# LTEW_User_Interface.net
KiCad netlist of a schematic drawn in Altium Designer
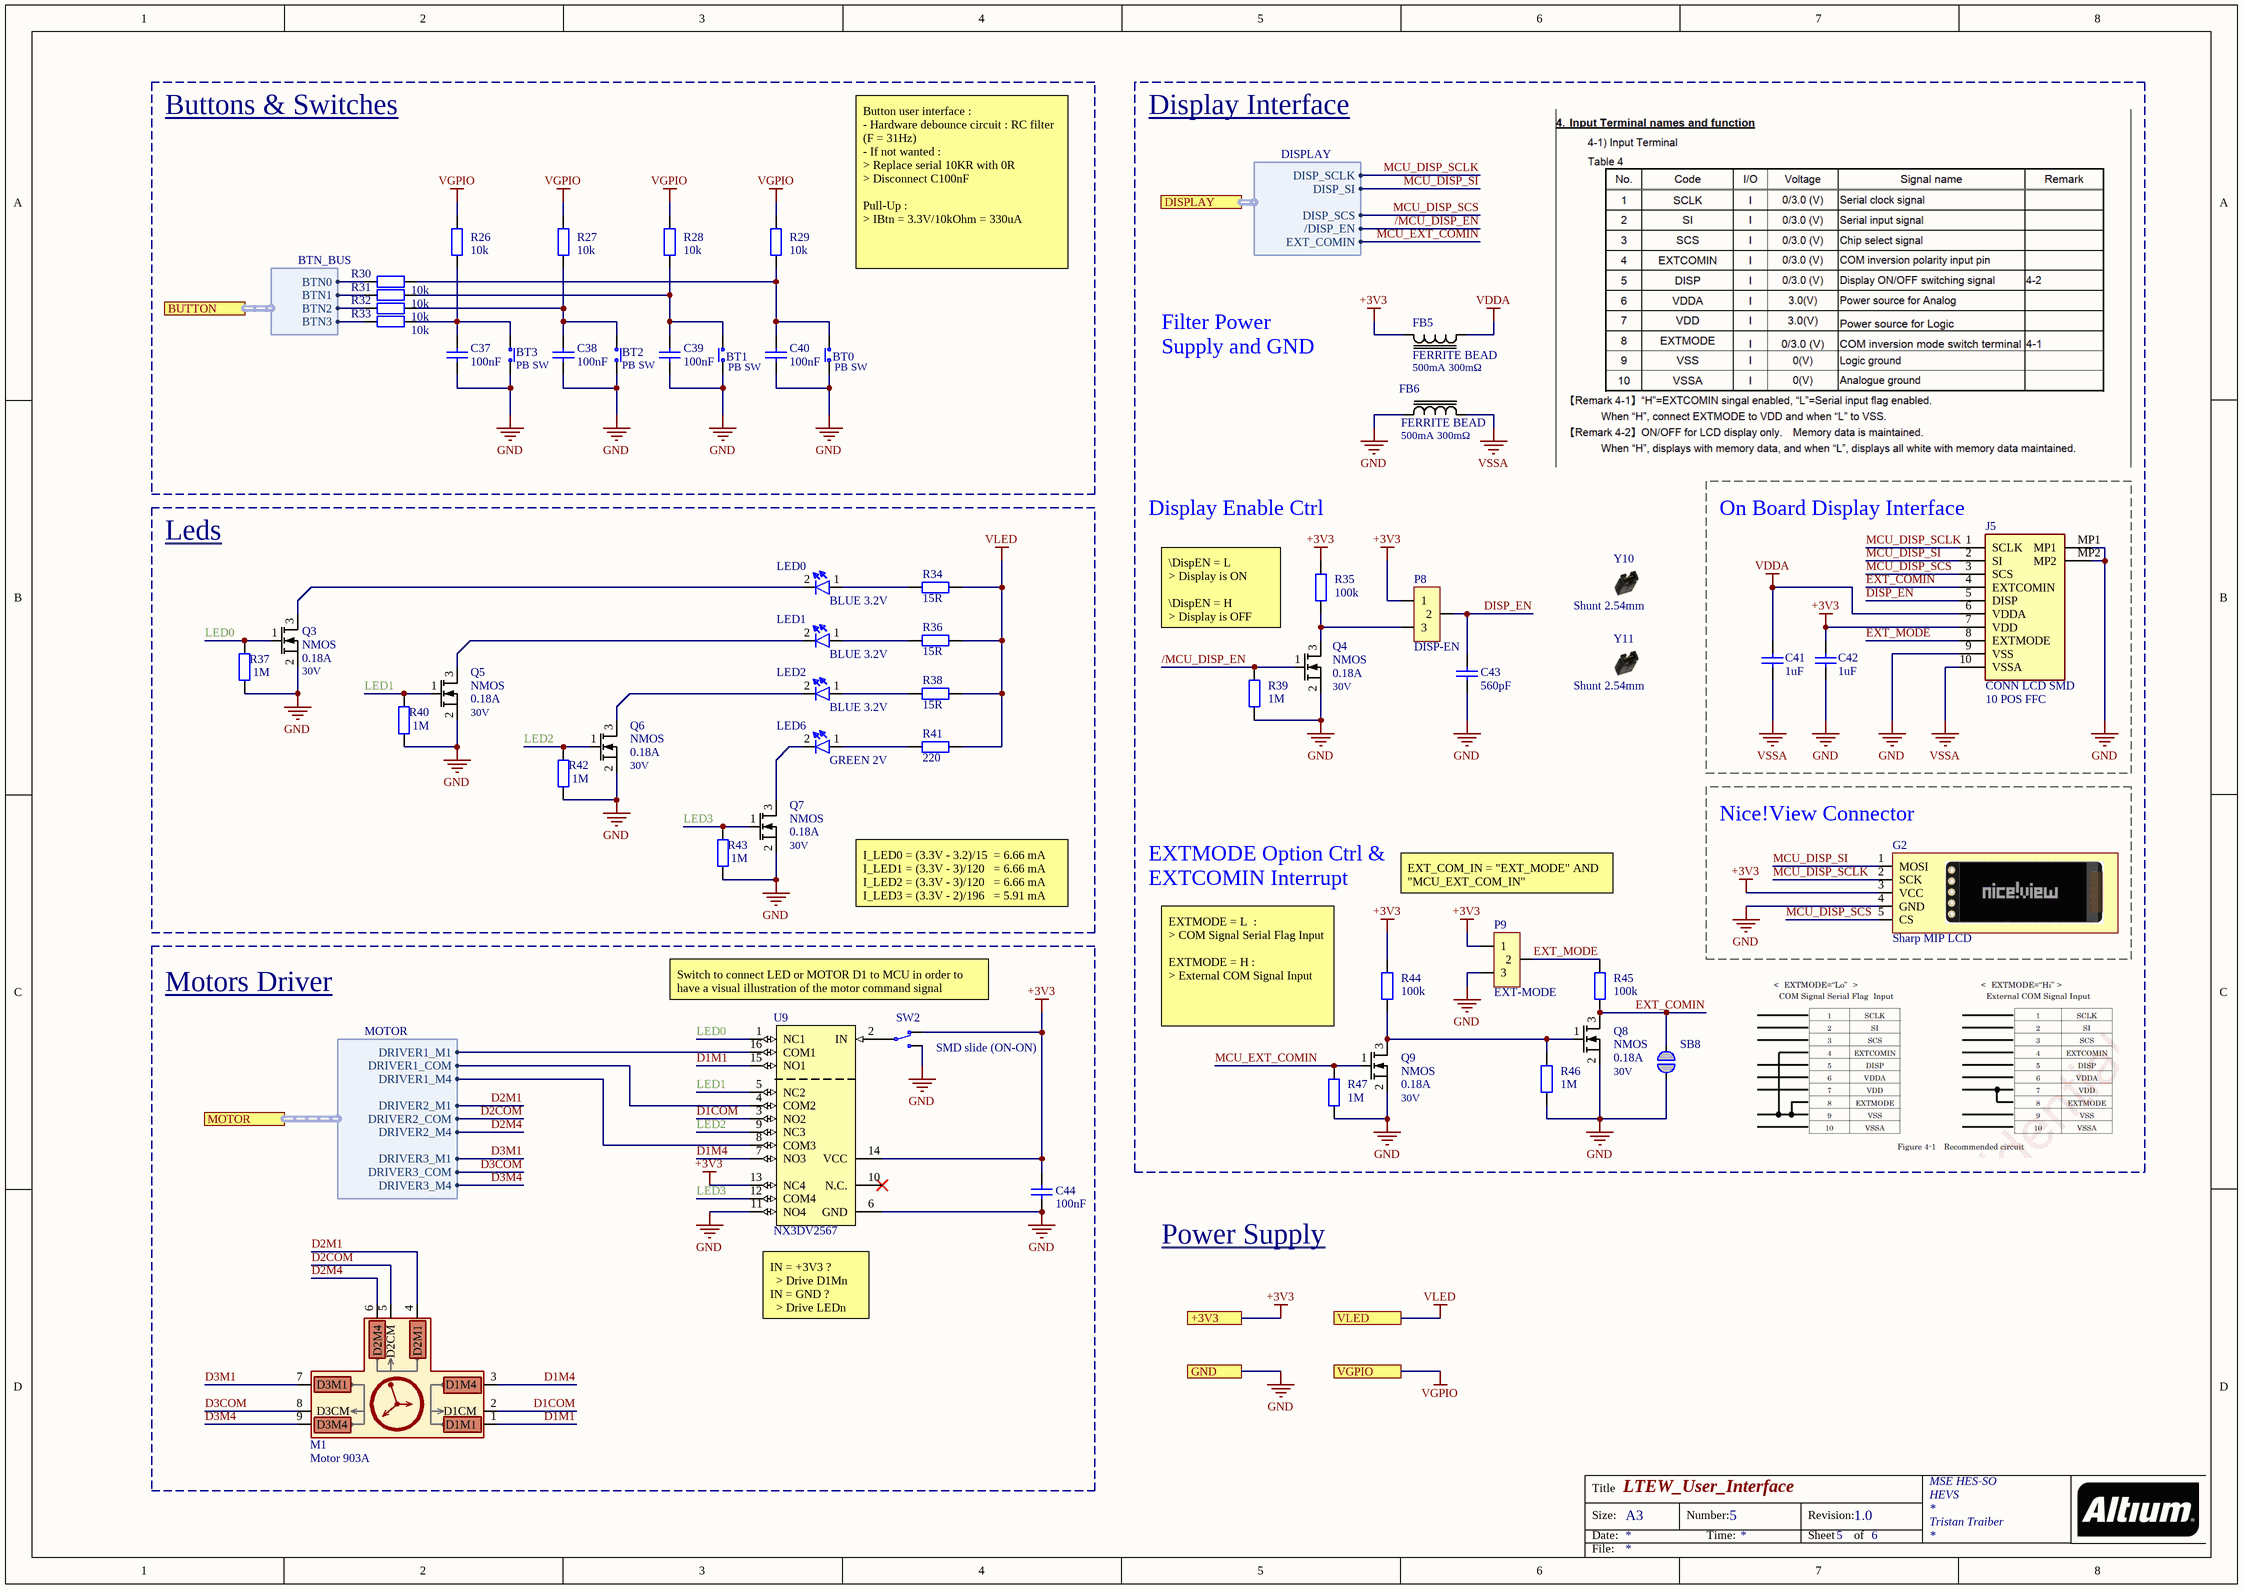
[diagram p0: LTEW_User_Interface.SchDoc]

(export (version "E")
  (design (tool "Eeschema 10.0.6"))
  (components
    (comp (ref "BT0")
      (value "PB SW")
      (footprint "Switch-PB-SMD-BT0")
      (description "Tactile Switch, SPNO, SMD, 160gf, 6.2x6.3x2.5mm")
      (fields (field (name "MANUFACTURER_PART_NUMBER") "SKHUALE010"))
      (libsource (lib "LTEWlib") (part "SW_SMD_PB"))
    )
    (comp (ref "BT1")
      (value "PB SW")
      (footprint "Switch-PB-SMD-BT1")
      (description "Tactile Switch, SPNO, SMD, 160gf, 6.2x6.3x2.5mm")
      (fields (field (name "MANUFACTURER_PART_NUMBER") "SKHUALE010"))
      (libsource (lib "LTEWlib") (part "SW_SMD_PB"))
    )
    (comp (ref "BT2")
      (value "PB SW")
      (footprint "Switch-PB-SMD-BT2")
      (description "Tactile Switch, SPNO, SMD, 160gf, 6.2x6.3x2.5mm")
      (fields (field (name "MANUFACTURER_PART_NUMBER") "SKHUALE010"))
      (libsource (lib "LTEWlib") (part "SW_SMD_PB"))
    )
    (comp (ref "BT3")
      (value "PB SW")
      (footprint "Switch-PB-SMD-BT3")
      (description "Tactile Switch, SPNO, SMD, 160gf, 6.2x6.3x2.5mm")
      (fields (field (name "MANUFACTURER_PART_NUMBER") "SKHUALE010"))
      (libsource (lib "LTEWlib") (part "SW_SMD_PB"))
    )
    (comp (ref "C37")
      (value "100nF")
      (footprint "C0603")
      (description "0.1 µF ±10% 25V Condensateurs céramique X7R 0603 (1608 métrique)")
      (fields (field (name "MANUFACTURER_PART_NUMBER") "CL10B104KA8NNNC"))
      (libsource (lib "LTEWlib") (part "C_100n"))
    )
    (comp (ref "C38")
      (value "100nF")
      (footprint "C0603")
      (description "0.1 µF ±10% 25V Condensateurs céramique X7R 0603 (1608 métrique)")
      (fields (field (name "MANUFACTURER_PART_NUMBER") "CL10B104KA8NNNC"))
      (libsource (lib "LTEWlib") (part "C_100n"))
    )
    (comp (ref "C39")
      (value "100nF")
      (footprint "C0603")
      (description "0.1 µF ±10% 25V Condensateurs céramique X7R 0603 (1608 métrique)")
      (fields (field (name "MANUFACTURER_PART_NUMBER") "CL10B104KA8NNNC"))
      (libsource (lib "LTEWlib") (part "C_100n"))
    )
    (comp (ref "C40")
      (value "100nF")
      (footprint "C0603")
      (description "0.1 µF ±10% 25V Condensateurs céramique X7R 0603 (1608 métrique)")
      (fields (field (name "MANUFACTURER_PART_NUMBER") "CL10B104KA8NNNC"))
      (libsource (lib "LTEWlib") (part "C_100n"))
    )
    (comp (ref "C41")
      (value "1uF")
      (footprint "C0603")
      (description "1 µF ±10% 25V Ceramic Capacitor X7R 0603 (1608 Metric)")
      (fields (field (name "MANUFACTURER_PART_NUMBER") "CL10B105KA8NNNC"))
      (libsource (lib "LTEWlib") (part "C_1u"))
    )
    (comp (ref "C42")
      (value "1uF")
      (footprint "C0603")
      (description "1 µF ±10% 25V Ceramic Capacitor X7R 0603 (1608 Metric)")
      (fields (field (name "MANUFACTURER_PART_NUMBER") "CL10B105KA8NNNC"))
      (libsource (lib "LTEWlib") (part "C_1u"))
    )
    (comp (ref "C43")
      (value "560pF")
      (footprint "C0603")
      (description "560 pF ±5% 25V Ceramic Capacitor C0G, NP0 0603 (1608 Metric)")
      (fields (field (name "MANUFACTURER_PART_NUMBER") "CC0603JRNPO8BN561"))
      (libsource (lib "LTEWlib") (part "C_560p"))
    )
    (comp (ref "C44")
      (value "100nF")
      (footprint "C0603")
      (description "0.1 µF ±10% 25V Condensateurs céramique X7R 0603 (1608 métrique)")
      (fields (field (name "MANUFACTURER_PART_NUMBER") "CL10B104KA8NNNC"))
      (libsource (lib "LTEWlib") (part "C_100n"))
    )
    (comp (ref "FB5")
      (value "FERRITE BEAD")
      (footprint "LTEWlib:BEADC2012X110N")
      (description "600 Ohms @ 100 MHz 1 Power, Signal Line Ferrite Bead 0805 (2012 Metric) 500mA 300mOhm")
      (fields
        (field (name "MANUFACTURER_PART_NUMBER") "HZ0805E601R-10")
        (field (name "ALTIUM_VALUE") "500mA 300mΩ")
      )
      (libsource (lib "LTEWlib") (part "L_FerritBead"))
    )
    (comp (ref "FB6")
      (value "FERRITE BEAD")
      (footprint "LTEWlib:BEADC2012X110N")
      (description "600 Ohms @ 100 MHz 1 Power, Signal Line Ferrite Bead 0805 (2012 Metric) 500mA 300mOhm")
      (fields
        (field (name "MANUFACTURER_PART_NUMBER") "HZ0805E601R-10")
        (field (name "ALTIUM_VALUE") "500mA 300mΩ")
      )
      (libsource (lib "LTEWlib") (part "L_FerritBead"))
    )
    (comp (ref "G2")
      (value "Sharp MIP LCD")
      (footprint "SHARP_MIP_LCD")
      (description "503535 3.8v 580mAh round lipo battery cells\r\n(Order : shorturl.at/tEFMZ)")
      (fields (field (name "MANUFACTURER_PART_NUMBER") "LS011B7DH03"))
      (libsource (lib "LTEWlib") (part "Display"))
    )
    (comp (ref "J5")
      (value "CONN LCD SMD")
      (footprint "LTEWlib:FH12A10S05SH55")
      (description "10 Position FFC, FPC Connector Contacts, Top 0.020\" (0.50mm) Surface Mount, Right Angle")
      (fields
        (field (name "MANUFACTURER_PART_NUMBER") "FH12A-10S-0.5SH(55)")
        (field (name "ALTIUM_VALUE") "10 POS FFC")
      )
      (libsource (lib "LTEWlib") (part "CONN_LCD_FFC12"))
    )
    (comp (ref "LED0")
      (value "BLUE 3.2V")
      (footprint "LTEWlib:LEDC1608X80N")
      (description "Blue 470nm LED Indication - Discrete 3.2V 0603 (1608 Metric)")
      (fields (field (name "MANUFACTURER_PART_NUMBER") "150060BS75000"))
      (libsource (lib "LTEWlib") (part "LED_B"))
    )
    (comp (ref "LED1")
      (value "BLUE 3.2V")
      (footprint "LTEWlib:LEDC1608X80N")
      (description "Blue 470nm LED Indication - Discrete 3.2V 0603 (1608 Metric)")
      (fields (field (name "MANUFACTURER_PART_NUMBER") "150060BS75000"))
      (libsource (lib "LTEWlib") (part "LED_B"))
    )
    (comp (ref "LED2")
      (value "BLUE 3.2V")
      (footprint "LTEWlib:LEDC1608X80N")
      (description "Blue 470nm LED Indication - Discrete 3.2V 0603 (1608 Metric)")
      (fields (field (name "MANUFACTURER_PART_NUMBER") "150060BS75000"))
      (libsource (lib "LTEWlib") (part "LED_B"))
    )
    (comp (ref "LED6")
      (value "GREEN 2V")
      (footprint "LTEWlib:LEDC1608X80N")
      (description "Green 570nm LED Indication - Discrete 2V 0603 (1608 Metric)")
      (fields (field (name "MANUFACTURER_PART_NUMBER") "150060VS75000"))
      (libsource (lib "LTEWlib") (part "LED_G"))
    )
    (comp (ref "M1")
      (value "Motor 903A")
      (footprint "MOTOR")
      (description "Titan 903A : 3 Hands Bidirectional, independent motor")
      (fields (field (name "PUBLISHER") "Altium Limited"))
      (libsource (lib "LTEWlib") (part "MOTOR_903A"))
    )
    (comp (ref "P8")
      (value "DISP-EN")
      (footprint "HDR1X3 - DISP_EN")
      (description "Header, 3-Pin")
      (fields (field (name "MANUFACTURER_PART_NUMBER") "M20-9990345"))
      (libsource (lib "LTEWlib") (part "H_3POS"))
    )
    (comp (ref "P9")
      (value "EXT-MODE")
      (footprint "HDR1X3 - EXT_MODE")
      (description "Header, 3-Pin")
      (fields (field (name "MANUFACTURER_PART_NUMBER") "M20-9990345"))
      (libsource (lib "LTEWlib") (part "H_3POS"))
    )
    (comp (ref "Q3")
      (value "NMOS")
      (footprint "LTEWlib:SOT65P210X110-3N")
      (description "N-Channel 30 V 180mA (Ta) 260mW (Ta), 1.1W (Tc) Surface Mount SOT-323")
      (fields
        (field (name "MANUFACTURER_PART_NUMBER") "NX3020NAKW")
        (field (name "VALUE2") "0.18A")
        (field (name "ALTIUM_VALUE") "30V")
      )
      (libsource (lib "LTEWlib") (part "MOS-N"))
    )
    (comp (ref "Q4")
      (value "NMOS")
      (footprint "LTEWlib:SOT65P210X110-3N")
      (description "N-Channel 30 V 180mA (Ta) 260mW (Ta), 1.1W (Tc) Surface Mount SOT-323")
      (fields
        (field (name "MANUFACTURER_PART_NUMBER") "NX3020NAKW")
        (field (name "VALUE2") "0.18A")
        (field (name "ALTIUM_VALUE") "30V")
      )
      (libsource (lib "LTEWlib") (part "MOS-N"))
    )
    (comp (ref "Q5")
      (value "NMOS")
      (footprint "LTEWlib:SOT65P210X110-3N")
      (description "N-Channel 30 V 180mA (Ta) 260mW (Ta), 1.1W (Tc) Surface Mount SOT-323")
      (fields
        (field (name "MANUFACTURER_PART_NUMBER") "NX3020NAKW")
        (field (name "VALUE2") "0.18A")
        (field (name "ALTIUM_VALUE") "30V")
      )
      (libsource (lib "LTEWlib") (part "MOS-N"))
    )
    (comp (ref "Q6")
      (value "NMOS")
      (footprint "LTEWlib:SOT65P210X110-3N")
      (description "N-Channel 30 V 180mA (Ta) 260mW (Ta), 1.1W (Tc) Surface Mount SOT-323")
      (fields
        (field (name "MANUFACTURER_PART_NUMBER") "NX3020NAKW")
        (field (name "VALUE2") "0.18A")
        (field (name "ALTIUM_VALUE") "30V")
      )
      (libsource (lib "LTEWlib") (part "MOS-N"))
    )
    (comp (ref "Q7")
      (value "NMOS")
      (footprint "LTEWlib:SOT65P210X110-3N")
      (description "N-Channel 30 V 180mA (Ta) 260mW (Ta), 1.1W (Tc) Surface Mount SOT-323")
      (fields
        (field (name "MANUFACTURER_PART_NUMBER") "NX3020NAKW")
        (field (name "VALUE2") "0.18A")
        (field (name "ALTIUM_VALUE") "30V")
      )
      (libsource (lib "LTEWlib") (part "MOS-N"))
    )
    (comp (ref "Q8")
      (value "NMOS")
      (footprint "LTEWlib:SOT65P210X110-3N")
      (description "N-Channel 30 V 180mA (Ta) 260mW (Ta), 1.1W (Tc) Surface Mount SOT-323")
      (fields
        (field (name "MANUFACTURER_PART_NUMBER") "NX3020NAKW")
        (field (name "VALUE2") "0.18A")
        (field (name "ALTIUM_VALUE") "30V")
      )
      (libsource (lib "LTEWlib") (part "MOS-N"))
    )
    (comp (ref "Q9")
      (value "NMOS")
      (footprint "LTEWlib:SOT65P210X110-3N")
      (description "N-Channel 30 V 180mA (Ta) 260mW (Ta), 1.1W (Tc) Surface Mount SOT-323")
      (fields
        (field (name "MANUFACTURER_PART_NUMBER") "NX3020NAKW")
        (field (name "VALUE2") "0.18A")
        (field (name "ALTIUM_VALUE") "30V")
      )
      (libsource (lib "LTEWlib") (part "MOS-N"))
    )
    (comp (ref "R26")
      (value "10k")
      (footprint "RES0603")
      (description "10 kOhms ±1% 0.1W, 1/10W Chip Resistor 0603 (1608 Metric) Moisture Resistant Thick Film")
      (fields (field (name "MANUFACTURER_PART_NUMBER") "RC0805FR-0710KL"))
      (libsource (lib "LTEWlib") (part "R_10k"))
    )
    (comp (ref "R27")
      (value "10k")
      (footprint "RES0603")
      (description "10 kOhms ±1% 0.1W, 1/10W Chip Resistor 0603 (1608 Metric) Moisture Resistant Thick Film")
      (fields (field (name "MANUFACTURER_PART_NUMBER") "RC0805FR-0710KL"))
      (libsource (lib "LTEWlib") (part "R_10k"))
    )
    (comp (ref "R28")
      (value "10k")
      (footprint "RES0603")
      (description "10 kOhms ±1% 0.1W, 1/10W Chip Resistor 0603 (1608 Metric) Moisture Resistant Thick Film")
      (fields (field (name "MANUFACTURER_PART_NUMBER") "RC0805FR-0710KL"))
      (libsource (lib "LTEWlib") (part "R_10k"))
    )
    (comp (ref "R29")
      (value "10k")
      (footprint "RES0603")
      (description "10 kOhms ±1% 0.1W, 1/10W Chip Resistor 0603 (1608 Metric) Moisture Resistant Thick Film")
      (fields (field (name "MANUFACTURER_PART_NUMBER") "RC0805FR-0710KL"))
      (libsource (lib "LTEWlib") (part "R_10k"))
    )
    (comp (ref "R30")
      (value "10k")
      (footprint "RES0603")
      (description "10 kOhms ±1% 0.1W, 1/10W Chip Resistor 0603 (1608 Metric) Moisture Resistant Thick Film")
      (fields (field (name "MANUFACTURER_PART_NUMBER") "RC0805FR-0710KL"))
      (libsource (lib "") (part "R_10k_1"))
    )
    (comp (ref "R31")
      (value "10k")
      (footprint "RES0603")
      (description "10 kOhms ±1% 0.1W, 1/10W Chip Resistor 0603 (1608 Metric) Moisture Resistant Thick Film")
      (fields (field (name "MANUFACTURER_PART_NUMBER") "RC0805FR-0710KL"))
      (libsource (lib "") (part "R_10k_1"))
    )
    (comp (ref "R32")
      (value "10k")
      (footprint "RES0603")
      (description "10 kOhms ±1% 0.1W, 1/10W Chip Resistor 0603 (1608 Metric) Moisture Resistant Thick Film")
      (fields (field (name "MANUFACTURER_PART_NUMBER") "RC0805FR-0710KL"))
      (libsource (lib "") (part "R_10k_1"))
    )
    (comp (ref "R33")
      (value "10k")
      (footprint "RES0603")
      (description "10 kOhms ±1% 0.1W, 1/10W Chip Resistor 0603 (1608 Metric) Moisture Resistant Thick Film")
      (fields (field (name "MANUFACTURER_PART_NUMBER") "RC0805FR-0710KL"))
      (libsource (lib "") (part "R_10k_1"))
    )
    (comp (ref "R34")
      (value "15R")
      (footprint "RES0603")
      (description "15 Ohms ±1% 0.1W, 1/10W Chip Resistor 0603 (1608 Metric) Moisture Resistant Thick Film")
      (fields (field (name "MANUFACTURER_PART_NUMBER") "RC0603FR-0715RL"))
      (libsource (lib "LTEWlib") (part "R_15"))
    )
    (comp (ref "R35")
      (value "100k")
      (footprint "RES0603")
      (description "RES SMD 100K OHM 1% 1/8W 0603")
      (fields (field (name "MANUFACTURER_PART_NUMBER") "RC0805FR-07100KL"))
      (libsource (lib "LTEWlib") (part "R_100k"))
    )
    (comp (ref "R36")
      (value "15R")
      (footprint "RES0603")
      (description "15 Ohms ±1% 0.1W, 1/10W Chip Resistor 0603 (1608 Metric) Moisture Resistant Thick Film")
      (fields (field (name "MANUFACTURER_PART_NUMBER") "RC0603FR-0715RL"))
      (libsource (lib "LTEWlib") (part "R_15"))
    )
    (comp (ref "R37")
      (value "1M")
      (footprint "RES0603")
      (description "1 MOhms ±1% 0.1W, 1/10W Chip Resistor 0603 (1608 Metric) Automotive AEC-Q200 Thick Film")
      (fields (field (name "MANUFACTURER_PART_NUMBER") "ERJ-3EKF1004V"))
      (libsource (lib "LTEWlib") (part "R_1M"))
    )
    (comp (ref "R38")
      (value "15R")
      (footprint "RES0603")
      (description "15 Ohms ±1% 0.1W, 1/10W Chip Resistor 0603 (1608 Metric) Moisture Resistant Thick Film")
      (fields (field (name "MANUFACTURER_PART_NUMBER") "RC0603FR-0715RL"))
      (libsource (lib "LTEWlib") (part "R_15"))
    )
    (comp (ref "R39")
      (value "1M")
      (footprint "RES0603")
      (description "1 MOhms ±1% 0.1W, 1/10W Chip Resistor 0603 (1608 Metric) Automotive AEC-Q200 Thick Film")
      (fields (field (name "MANUFACTURER_PART_NUMBER") "ERJ-3EKF1004V"))
      (libsource (lib "LTEWlib") (part "R_1M"))
    )
    (comp (ref "R40")
      (value "1M")
      (footprint "RES0603")
      (description "1 MOhms ±1% 0.1W, 1/10W Chip Resistor 0603 (1608 Metric) Automotive AEC-Q200 Thick Film")
      (fields (field (name "MANUFACTURER_PART_NUMBER") "ERJ-3EKF1004V"))
      (libsource (lib "LTEWlib") (part "R_1M"))
    )
    (comp (ref "R41")
      (value "220")
      (footprint "RES0603")
      (description "220 Ohms ±1% 0.1W, 1/10W Chip Resistor 0603 (1608 Metric) Moisture Resistant Thick Film")
      (fields (field (name "MANUFACTURER_PART_NUMBER") "CR0603-FX-3300ELF"))
      (libsource (lib "LTEWlib") (part "R_220"))
    )
    (comp (ref "R42")
      (value "1M")
      (footprint "RES0603")
      (description "1 MOhms ±1% 0.1W, 1/10W Chip Resistor 0603 (1608 Metric) Automotive AEC-Q200 Thick Film")
      (fields (field (name "MANUFACTURER_PART_NUMBER") "ERJ-3EKF1004V"))
      (libsource (lib "LTEWlib") (part "R_1M"))
    )
    (comp (ref "R43")
      (value "1M")
      (footprint "RES0603")
      (description "1 MOhms ±1% 0.1W, 1/10W Chip Resistor 0603 (1608 Metric) Automotive AEC-Q200 Thick Film")
      (fields (field (name "MANUFACTURER_PART_NUMBER") "ERJ-3EKF1004V"))
      (libsource (lib "LTEWlib") (part "R_1M"))
    )
    (comp (ref "R44")
      (value "100k")
      (footprint "RES0603")
      (description "RES SMD 100K OHM 1% 1/8W 0603")
      (fields (field (name "MANUFACTURER_PART_NUMBER") "RC0805FR-07100KL"))
      (libsource (lib "LTEWlib") (part "R_100k"))
    )
    (comp (ref "R45")
      (value "100k")
      (footprint "RES0603")
      (description "RES SMD 100K OHM 1% 1/8W 0603")
      (fields (field (name "MANUFACTURER_PART_NUMBER") "RC0805FR-07100KL"))
      (libsource (lib "LTEWlib") (part "R_100k"))
    )
    (comp (ref "R46")
      (value "1M")
      (footprint "RES0603")
      (description "1 MOhms ±1% 0.1W, 1/10W Chip Resistor 0603 (1608 Metric) Automotive AEC-Q200 Thick Film")
      (fields (field (name "MANUFACTURER_PART_NUMBER") "ERJ-3EKF1004V"))
      (libsource (lib "LTEWlib") (part "R_1M"))
    )
    (comp (ref "R47")
      (value "1M")
      (footprint "RES0603")
      (description "1 MOhms ±1% 0.1W, 1/10W Chip Resistor 0603 (1608 Metric) Automotive AEC-Q200 Thick Film")
      (fields (field (name "MANUFACTURER_PART_NUMBER") "ERJ-3EKF1004V"))
      (libsource (lib "LTEWlib") (part "R_1M"))
    )
    (comp (ref "SB8")
      (value "Solderbridge")
      (footprint "Solderbridge")
      (fields (field (name "MANUFACTURER") "N.A."))
      (libsource (lib "pca10090") (part "Solderbridge"))
    )
    (comp (ref "SW2")
      (value "SMD slide (ON-ON)")
      (footprint "CJS-120xA - M/L")
      (description "SMD slide Switch (ON-ON)")
      (fields (field (name "MANUFACTURER_PART_NUMBER") "CJS-1200TA"))
      (libsource (lib "LTEWlib") (part "SW_2POS"))
    )
    (comp (ref "U9")
      (value "NX3DV2567")
      (footprint "XQFN40P180X260X50-16N")
      (description "Low-ohmic four-pole double-throw analog switch")
      (fields (field (name "MANUFACTURER PART NUMBER") "NX3DV2567GU"))
      (libsource (lib "LTEWlib") (part "NX3DV2567GU"))
    )
    (comp (ref "Y10")
      (value "Shunt 2.54mm")
      (footprint "Shunt_2.54mm_Horizontal")
      (description "Shunt Jumper 2.54mm Black")
      (fields (field (name "MANUFACTURER PART NUMBER") "SPC02SYAN"))
      (libsource (lib "LTEWlib") (part "SHUNT JUMPER 2.54mm BLACK GOLD Horizontal"))
    )
    (comp (ref "Y11")
      (value "Shunt 2.54mm")
      (footprint "Shunt_2.54mm_Horizontal")
      (description "Shunt Jumper 2.54mm Black")
      (fields (field (name "MANUFACTURER PART NUMBER") "SPC02SYAN"))
      (libsource (lib "LTEWlib") (part "SHUNT JUMPER 2.54mm BLACK GOLD Horizontal"))
    )
  )
  (nets
    (net (code "4") (name "+3V3") (class "Default")
      (node (ref "C42") (pin "2") (pinfunction "2_2") (pintype "passive"))
      (node (ref "C44") (pin "2") (pinfunction "2_2") (pintype "passive"))
      (node (ref "FB5") (pin "2") (pinfunction "2_2") (pintype "passive"))
      (node (ref "G2") (pin "3") (pinfunction "VCC_3") (pintype "passive"))
      (node (ref "J5") (pin "7") (pinfunction "VDD_7") (pintype "passive"))
      (node (ref "P8") (pin "1") (pinfunction "1_1") (pintype "passive"))
      (node (ref "P9") (pin "1") (pinfunction "1_1") (pintype "passive"))
      (node (ref "R35") (pin "2") (pinfunction "2_2") (pintype "passive"))
      (node (ref "R44") (pin "2") (pinfunction "2_2") (pintype "passive"))
      (node (ref "SW2") (pin "1") (pinfunction "N.C_1") (pintype "passive"))
      (node (ref "U9") (pin "13") (pinfunction "NC4_13") (pintype "bidirectional"))
      (node (ref "U9") (pin "14") (pinfunction "VCC_14") (pintype "power_in"))
    )
    (net (code "5") (name "/BTN0") (class "Default")
      (node (ref "R30") (pin "1") (pinfunction "1_1") (pintype "passive"))
    )
    (net (code "6") (name "/BTN1") (class "Default")
      (node (ref "R31") (pin "1") (pinfunction "1_1") (pintype "passive"))
    )
    (net (code "7") (name "/BTN2") (class "Default")
      (node (ref "R32") (pin "1") (pinfunction "1_1") (pintype "passive"))
    )
    (net (code "8") (name "/BTN3") (class "Default")
      (node (ref "R33") (pin "1") (pinfunction "1_1") (pintype "passive"))
    )
    (net (code "9") (name "/D1COM") (class "Default")
      (node (ref "M1") (pin "2") (pinfunction "D1CM_2") (pintype "passive"))
      (node (ref "U9") (pin "3") (pinfunction "NO2_3") (pintype "bidirectional"))
    )
    (net (code "10") (name "/D1M1") (class "Default")
      (node (ref "M1") (pin "1") (pinfunction "D1M1_1") (pintype "passive"))
      (node (ref "U9") (pin "15") (pinfunction "NO1_15") (pintype "bidirectional"))
    )
    (net (code "11") (name "/D1M4") (class "Default")
      (node (ref "M1") (pin "3") (pinfunction "D1M4_3") (pintype "passive"))
      (node (ref "U9") (pin "7") (pinfunction "NO3_7") (pintype "bidirectional"))
    )
    (net (code "12") (name "/D2COM") (class "Default")
      (node (ref "M1") (pin "5") (pinfunction "D2CM_5") (pintype "passive"))
    )
    (net (code "13") (name "/D2M1") (class "Default")
      (node (ref "M1") (pin "4") (pinfunction "D2M1_4") (pintype "passive"))
    )
    (net (code "14") (name "/D2M4") (class "Default")
      (node (ref "M1") (pin "6") (pinfunction "D2M4_6") (pintype "passive"))
    )
    (net (code "15") (name "/D3COM") (class "Default")
      (node (ref "M1") (pin "8") (pinfunction "D3CM_8") (pintype "passive"))
    )
    (net (code "16") (name "/D3M1") (class "Default")
      (node (ref "M1") (pin "7") (pinfunction "D3M1_7") (pintype "passive"))
    )
    (net (code "17") (name "/D3M4") (class "Default")
      (node (ref "M1") (pin "9") (pinfunction "D3M4_9") (pintype "passive"))
    )
    (net (code "18") (name "/DISP_EN") (class "Default")
      (node (ref "C43") (pin "2") (pinfunction "2_2") (pintype "passive"))
      (node (ref "J5") (pin "5") (pinfunction "DISP_5") (pintype "passive"))
      (node (ref "P8") (pin "2") (pinfunction "2_2") (pintype "passive"))
    )
    (net (code "19") (name "/DRIVER1_COM") (class "Default")
      (node (ref "U9") (pin "4") (pinfunction "COM2_4") (pintype "bidirectional"))
    )
    (net (code "20") (name "/DRIVER1_M1") (class "Default")
      (node (ref "U9") (pin "16") (pinfunction "COM1_16") (pintype "bidirectional"))
    )
    (net (code "21") (name "/DRIVER1_M4") (class "Default")
      (node (ref "U9") (pin "8") (pinfunction "COM3_8") (pintype "bidirectional"))
    )
    (net (code "22") (name "/EXT_COMIN") (class "Default")
      (node (ref "J5") (pin "4") (pinfunction "EXTCOMIN_4") (pintype "passive"))
      (node (ref "Q8") (pin "3") (pinfunction "D_3") (pintype "passive"))
      (node (ref "R45") (pin "1") (pinfunction "1_1") (pintype "passive"))
      (node (ref "SB8") (pin "1") (pinfunction "0_1") (pintype "passive"))
    )
    (net (code "23") (name "/EXT_MODE") (class "Default")
      (node (ref "J5") (pin "8") (pinfunction "EXTMODE_8") (pintype "passive"))
      (node (ref "P9") (pin "2") (pinfunction "2_2") (pintype "passive"))
      (node (ref "R45") (pin "2") (pinfunction "2_2") (pintype "passive"))
    )
    (net (code "24") (name "/LED0") (class "Default")
      (node (ref "Q3") (pin "1") (pinfunction "G_1") (pintype "passive"))
      (node (ref "R37") (pin "2") (pinfunction "2_2") (pintype "passive"))
      (node (ref "U9") (pin "1") (pinfunction "NC1_1") (pintype "bidirectional"))
    )
    (net (code "25") (name "/LED1") (class "Default")
      (node (ref "Q5") (pin "1") (pinfunction "G_1") (pintype "passive"))
      (node (ref "R40") (pin "2") (pinfunction "2_2") (pintype "passive"))
      (node (ref "U9") (pin "5") (pinfunction "NC2_5") (pintype "bidirectional"))
    )
    (net (code "26") (name "/LED2") (class "Default")
      (node (ref "Q6") (pin "1") (pinfunction "G_1") (pintype "passive"))
      (node (ref "R42") (pin "2") (pinfunction "2_2") (pintype "passive"))
      (node (ref "U9") (pin "9") (pinfunction "NC3_9") (pintype "bidirectional"))
    )
    (net (code "27") (name "/LED3") (class "Default")
      (node (ref "Q7") (pin "1") (pinfunction "G_1") (pintype "passive"))
      (node (ref "R43") (pin "2") (pinfunction "2_2") (pintype "passive"))
      (node (ref "U9") (pin "12") (pinfunction "COM4_12") (pintype "bidirectional"))
    )
    (net (code "28") (name "/MCU_DISP_SCLK") (class "Default")
      (node (ref "G2") (pin "2") (pinfunction "SCK_2") (pintype "passive"))
      (node (ref "J5") (pin "1") (pinfunction "SCLK_1") (pintype "passive"))
    )
    (net (code "29") (name "/MCU_DISP_SCS") (class "Default")
      (node (ref "G2") (pin "5") (pinfunction "CS_5") (pintype "passive"))
      (node (ref "J5") (pin "3") (pinfunction "SCS_3") (pintype "passive"))
    )
    (net (code "30") (name "/MCU_DISP_SI") (class "Default")
      (node (ref "G2") (pin "1") (pinfunction "MOSI_1") (pintype "passive"))
      (node (ref "J5") (pin "2") (pinfunction "SI_2") (pintype "passive"))
    )
    (net (code "31") (name "/MCU_EXT_COMIN") (class "Default")
      (node (ref "Q9") (pin "1") (pinfunction "G_1") (pintype "passive"))
      (node (ref "R47") (pin "2") (pinfunction "2_2") (pintype "passive"))
    )
    (net (code "35") (name "/{slash}MCU_DISP_EN") (class "Default")
      (node (ref "Q4") (pin "1") (pinfunction "G_1") (pintype "passive"))
      (node (ref "R39") (pin "2") (pinfunction "2_2") (pintype "passive"))
    )
    (net (code "36") (name "GND") (class "Default")
      (node (ref "BT0") (pin "2") (pinfunction "COM_2") (pintype "passive"))
      (node (ref "BT1") (pin "2") (pinfunction "COM_2") (pintype "passive"))
      (node (ref "BT2") (pin "1") (pinfunction "N.O_1") (pintype "passive"))
      (node (ref "BT3") (pin "1") (pinfunction "N.O_1") (pintype "passive"))
      (node (ref "C37") (pin "1") (pinfunction "1_1") (pintype "passive"))
      (node (ref "C38") (pin "1") (pinfunction "1_1") (pintype "passive"))
      (node (ref "C39") (pin "1") (pinfunction "1_1") (pintype "passive"))
      (node (ref "C40") (pin "1") (pinfunction "1_1") (pintype "passive"))
      (node (ref "C42") (pin "1") (pinfunction "1_1") (pintype "passive"))
      (node (ref "C43") (pin "1") (pinfunction "1_1") (pintype "passive"))
      (node (ref "C44") (pin "1") (pinfunction "1_1") (pintype "passive"))
      (node (ref "FB6") (pin "1") (pinfunction "1_1") (pintype "passive"))
      (node (ref "G2") (pin "4") (pinfunction "GND_4") (pintype "passive"))
      (node (ref "J5") (pin "9") (pinfunction "VSS_9") (pintype "passive"))
      (node (ref "J5") (pin "MP1") (pinfunction "MP1_MP1") (pintype "passive"))
      (node (ref "J5") (pin "MP2") (pinfunction "MP2_MP2") (pintype "passive"))
      (node (ref "P9") (pin "3") (pinfunction "3_3") (pintype "passive"))
      (node (ref "Q3") (pin "2") (pinfunction "S_2") (pintype "passive"))
      (node (ref "Q4") (pin "2") (pinfunction "S_2") (pintype "passive"))
      (node (ref "Q5") (pin "2") (pinfunction "S_2") (pintype "passive"))
      (node (ref "Q6") (pin "2") (pinfunction "S_2") (pintype "passive"))
      (node (ref "Q7") (pin "2") (pinfunction "S_2") (pintype "passive"))
      (node (ref "Q8") (pin "2") (pinfunction "S_2") (pintype "passive"))
      (node (ref "Q9") (pin "2") (pinfunction "S_2") (pintype "passive"))
      (node (ref "R37") (pin "1") (pinfunction "1_1") (pintype "passive"))
      (node (ref "R39") (pin "1") (pinfunction "1_1") (pintype "passive"))
      (node (ref "R40") (pin "1") (pinfunction "1_1") (pintype "passive"))
      (node (ref "R42") (pin "1") (pinfunction "1_1") (pintype "passive"))
      (node (ref "R43") (pin "1") (pinfunction "1_1") (pintype "passive"))
      (node (ref "R46") (pin "1") (pinfunction "1_1") (pintype "passive"))
      (node (ref "R47") (pin "1") (pinfunction "1_1") (pintype "passive"))
      (node (ref "SB8") (pin "2") (pinfunction "1_2") (pintype "passive"))
      (node (ref "SW2") (pin "3") (pinfunction "N.O_3") (pintype "passive"))
      (node (ref "U9") (pin "11") (pinfunction "NO4_11") (pintype "bidirectional"))
      (node (ref "U9") (pin "6") (pinfunction "GND_6") (pintype "power_in"))
    )
    (net (code "37") (name "Net-(BT0-N.O)") (class "Default")
      (node (ref "BT0") (pin "1") (pinfunction "N.O_1") (pintype "passive"))
      (node (ref "C40") (pin "2") (pinfunction "2_2") (pintype "passive"))
      (node (ref "R29") (pin "1") (pinfunction "1_1") (pintype "passive"))
      (node (ref "R30") (pin "2") (pinfunction "2_2") (pintype "passive"))
    )
    (net (code "38") (name "Net-(BT1-N.O)") (class "Default")
      (node (ref "BT1") (pin "1") (pinfunction "N.O_1") (pintype "passive"))
      (node (ref "C39") (pin "2") (pinfunction "2_2") (pintype "passive"))
      (node (ref "R28") (pin "1") (pinfunction "1_1") (pintype "passive"))
      (node (ref "R31") (pin "2") (pinfunction "2_2") (pintype "passive"))
    )
    (net (code "39") (name "Net-(BT2-COM)") (class "Default")
      (node (ref "BT2") (pin "2") (pinfunction "COM_2") (pintype "passive"))
      (node (ref "C38") (pin "2") (pinfunction "2_2") (pintype "passive"))
      (node (ref "R27") (pin "1") (pinfunction "1_1") (pintype "passive"))
      (node (ref "R32") (pin "2") (pinfunction "2_2") (pintype "passive"))
    )
    (net (code "40") (name "Net-(BT3-COM)") (class "Default")
      (node (ref "BT3") (pin "2") (pinfunction "COM_2") (pintype "passive"))
      (node (ref "C37") (pin "2") (pinfunction "2_2") (pintype "passive"))
      (node (ref "R26") (pin "1") (pinfunction "1_1") (pintype "passive"))
      (node (ref "R33") (pin "2") (pinfunction "2_2") (pintype "passive"))
    )
    (net (code "41") (name "Net-(LED0-A)") (class "Default")
      (node (ref "LED0") (pin "1") (pinfunction "A_1") (pintype "passive"))
      (node (ref "R34") (pin "1") (pinfunction "1_1") (pintype "passive"))
    )
    (net (code "42") (name "Net-(LED0-K)") (class "Default")
      (node (ref "LED0") (pin "2") (pinfunction "K_2") (pintype "passive"))
      (node (ref "Q3") (pin "3") (pinfunction "D_3") (pintype "passive"))
    )
    (net (code "43") (name "Net-(LED1-A)") (class "Default")
      (node (ref "LED1") (pin "1") (pinfunction "A_1") (pintype "passive"))
      (node (ref "R36") (pin "1") (pinfunction "1_1") (pintype "passive"))
    )
    (net (code "44") (name "Net-(LED1-K)") (class "Default")
      (node (ref "LED1") (pin "2") (pinfunction "K_2") (pintype "passive"))
      (node (ref "Q5") (pin "3") (pinfunction "D_3") (pintype "passive"))
    )
    (net (code "45") (name "Net-(LED2-A)") (class "Default")
      (node (ref "LED2") (pin "1") (pinfunction "A_1") (pintype "passive"))
      (node (ref "R38") (pin "1") (pinfunction "1_1") (pintype "passive"))
    )
    (net (code "46") (name "Net-(LED2-K)") (class "Default")
      (node (ref "LED2") (pin "2") (pinfunction "K_2") (pintype "passive"))
      (node (ref "Q6") (pin "3") (pinfunction "D_3") (pintype "passive"))
    )
    (net (code "47") (name "Net-(LED6-A)") (class "Default")
      (node (ref "LED6") (pin "1") (pinfunction "A_1") (pintype "passive"))
      (node (ref "R41") (pin "1") (pinfunction "1_1") (pintype "passive"))
    )
    (net (code "48") (name "Net-(LED6-K)") (class "Default")
      (node (ref "LED6") (pin "2") (pinfunction "K_2") (pintype "passive"))
      (node (ref "Q7") (pin "3") (pinfunction "D_3") (pintype "passive"))
    )
    (net (code "49") (name "Net-(Q4-D)") (class "Default")
      (node (ref "P8") (pin "3") (pinfunction "3_3") (pintype "passive"))
      (node (ref "Q4") (pin "3") (pinfunction "D_3") (pintype "passive"))
      (node (ref "R35") (pin "1") (pinfunction "1_1") (pintype "passive"))
    )
    (net (code "50") (name "Net-(Q8-G)") (class "Default")
      (node (ref "Q8") (pin "1") (pinfunction "G_1") (pintype "passive"))
      (node (ref "Q9") (pin "3") (pinfunction "D_3") (pintype "passive"))
      (node (ref "R44") (pin "1") (pinfunction "1_1") (pintype "passive"))
      (node (ref "R46") (pin "2") (pinfunction "2_2") (pintype "passive"))
    )
    (net (code "51") (name "Net-(SW2-COM)") (class "Default")
      (node (ref "SW2") (pin "2") (pinfunction "COM_2") (pintype "passive"))
      (node (ref "U9") (pin "2") (pinfunction "IN_2") (pintype "input"))
    )
    (net (code "52") (name "VDDA") (class "Default")
      (node (ref "C41") (pin "2") (pinfunction "2_2") (pintype "passive"))
      (node (ref "FB5") (pin "1") (pinfunction "1_1") (pintype "passive"))
      (node (ref "J5") (pin "6") (pinfunction "VDDA_6") (pintype "passive"))
    )
    (net (code "53") (name "VGPIO") (class "Default")
      (node (ref "R26") (pin "2") (pinfunction "2_2") (pintype "passive"))
      (node (ref "R27") (pin "2") (pinfunction "2_2") (pintype "passive"))
      (node (ref "R28") (pin "2") (pinfunction "2_2") (pintype "passive"))
      (node (ref "R29") (pin "2") (pinfunction "2_2") (pintype "passive"))
    )
    (net (code "54") (name "VLED") (class "Default")
      (node (ref "R34") (pin "2") (pinfunction "2_2") (pintype "passive"))
      (node (ref "R36") (pin "2") (pinfunction "2_2") (pintype "passive"))
      (node (ref "R38") (pin "2") (pinfunction "2_2") (pintype "passive"))
      (node (ref "R41") (pin "2") (pinfunction "2_2") (pintype "passive"))
    )
    (net (code "55") (name "VSSA") (class "Default")
      (node (ref "C41") (pin "1") (pinfunction "1_1") (pintype "passive"))
      (node (ref "FB6") (pin "2") (pinfunction "2_2") (pintype "passive"))
      (node (ref "J5") (pin "10") (pinfunction "VSSA_10") (pintype "passive"))
    )
    (net (code "56") (name "unconnected-(U9-N.C.-Pad10)") (class "Default")
      (node (ref "U9") (pin "10") (pinfunction "N.C._10") (pintype "passive+no_connect"))
    )
  )
)
